# UPC2710TB.net
KiCad netlist of a schematic drawn in Altium Designer
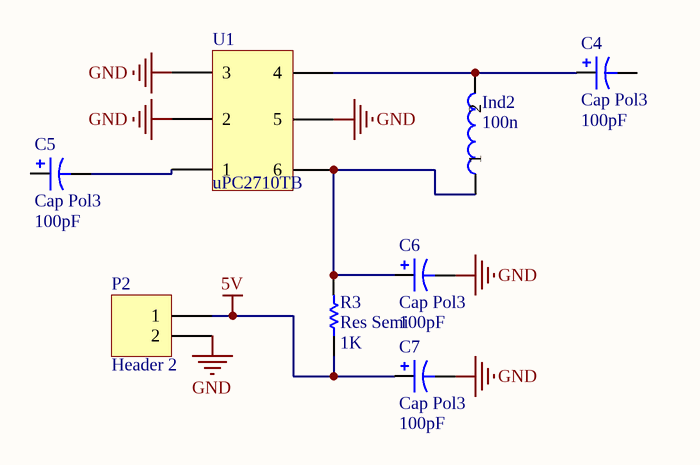
[diagram p0: UPC2710TB.SchDoc]

(export (version "E")
  (design (tool "Eeschema 10.0.6"))
  (components
    (comp (ref "C4")
      (value "Cap Pol3")
      (footprint "C0805")
      (description "Polarized Capacitor (Surface Mount)")
      (fields (field (name "ALTIUM_VALUE") "100pF") (field (name "PUBLISHER") "Altium Limited"))
      (libsource (lib "Miscellaneous Devices") (part "Cap Pol3"))
    )
    (comp (ref "C5")
      (value "Cap Pol3")
      (footprint "C0805")
      (description "Polarized Capacitor (Surface Mount)")
      (fields (field (name "ALTIUM_VALUE") "100pF") (field (name "PUBLISHER") "Altium Limited"))
      (libsource (lib "Miscellaneous Devices") (part "Cap Pol3"))
    )
    (comp (ref "C6")
      (value "Cap Pol3")
      (footprint "C0805")
      (description "Polarized Capacitor (Surface Mount)")
      (fields (field (name "ALTIUM_VALUE") "100pF") (field (name "PUBLISHER") "Altium Limited"))
      (libsource (lib "Miscellaneous Devices") (part "Cap Pol3"))
    )
    (comp (ref "C7")
      (value "Cap Pol3")
      (footprint "C0805")
      (description "Polarized Capacitor (Surface Mount)")
      (fields (field (name "ALTIUM_VALUE") "100pF") (field (name "PUBLISHER") "Altium Limited"))
      (libsource (lib "Miscellaneous Devices") (part "Cap Pol3"))
    )
    (comp (ref "Ind2")
      (value "Ind2")
      (footprint "Ind_5mm")
      (fields (field (name "VALOR") "100n"))
      (libsource (lib "epf") (part "Ind2"))
    )
    (comp (ref "P2")
      (value "Header 2")
      (footprint "HDR1X2")
      (description "Header, 2-Pin")
      (fields (field (name "PUBLISHER") "Altium Limited"))
      (libsource (lib "Miscellaneous Connectors") (part "Header 2"))
    )
    (comp (ref "R3")
      (value "Res Semi")
      (footprint "2012[0805]")
      (description "Semiconductor Resistor")
      (fields (field (name "ALTIUM_VALUE") "1K") (field (name "PUBLISHER") "Altium Limited"))
      (libsource (lib "Miscellaneous Devices") (part "Res Semi"))
    )
    (comp (ref "U1") (value "uPC2710TB") (footprint "UPC2710TB2") (libsource (lib "epf") (part "uPC2710TB")))
  )
  (nets
    (net (code "1") (name "5V") (class "Default")
      (node (ref "C7") (pin "1") (pinfunction "1_1") (pintype "passive"))
      (node (ref "P2") (pin "1") (pinfunction "1_1") (pintype "passive"))
      (node (ref "R3") (pin "1") (pinfunction "1_1") (pintype "passive"))
    )
    (net (code "2") (name "GND") (class "Default")
      (node (ref "C6") (pin "2") (pinfunction "2_2") (pintype "passive"))
      (node (ref "C7") (pin "2") (pinfunction "2_2") (pintype "passive"))
      (node (ref "P2") (pin "2") (pinfunction "2_2") (pintype "passive"))
      (node (ref "U1") (pin "GND1") (pinfunction "2_GND1") (pintype "passive"))
      (node (ref "U1") (pin "GND2") (pinfunction "3_GND2") (pintype "passive"))
      (node (ref "U1") (pin "GND3") (pinfunction "5_GND3") (pintype "passive"))
    )
    (net (code "3") (name "Net-(U1-1)") (class "Default")
      (node (ref "C5") (pin "2") (pinfunction "2_2") (pintype "passive"))
      (node (ref "U1") (pin "RF_IN") (pinfunction "1_RF_IN") (pintype "passive"))
    )
    (net (code "4") (name "Net-(U1-4)") (class "Default")
      (node (ref "C4") (pin "1") (pinfunction "1_1") (pintype "passive"))
      (node (ref "Ind2") (pin "2") (pinfunction "2_2") (pintype "passive"))
      (node (ref "U1") (pin "RF_OUT") (pinfunction "4_RF_OUT") (pintype "passive"))
    )
    (net (code "5") (name "Net-(U1-6)") (class "Default")
      (node (ref "C6") (pin "1") (pinfunction "1_1") (pintype "passive"))
      (node (ref "Ind2") (pin "1") (pinfunction "1_1") (pintype "passive"))
      (node (ref "R3") (pin "2") (pinfunction "2_2") (pintype "passive"))
      (node (ref "U1") (pin "Vcc") (pinfunction "6_Vcc") (pintype "passive"))
    )
    (net (code "6") (name "unconnected-(C4-Pad2)") (class "Default")
      (node (ref "C4") (pin "2") (pinfunction "2_2") (pintype "passive"))
    )
    (net (code "7") (name "unconnected-(C5-Pad1)") (class "Default")
      (node (ref "C5") (pin "1") (pinfunction "1_1") (pintype "passive"))
    )
  )
)
